# sensor.net
KiCad netlist of a schematic drawn in Altium Designer
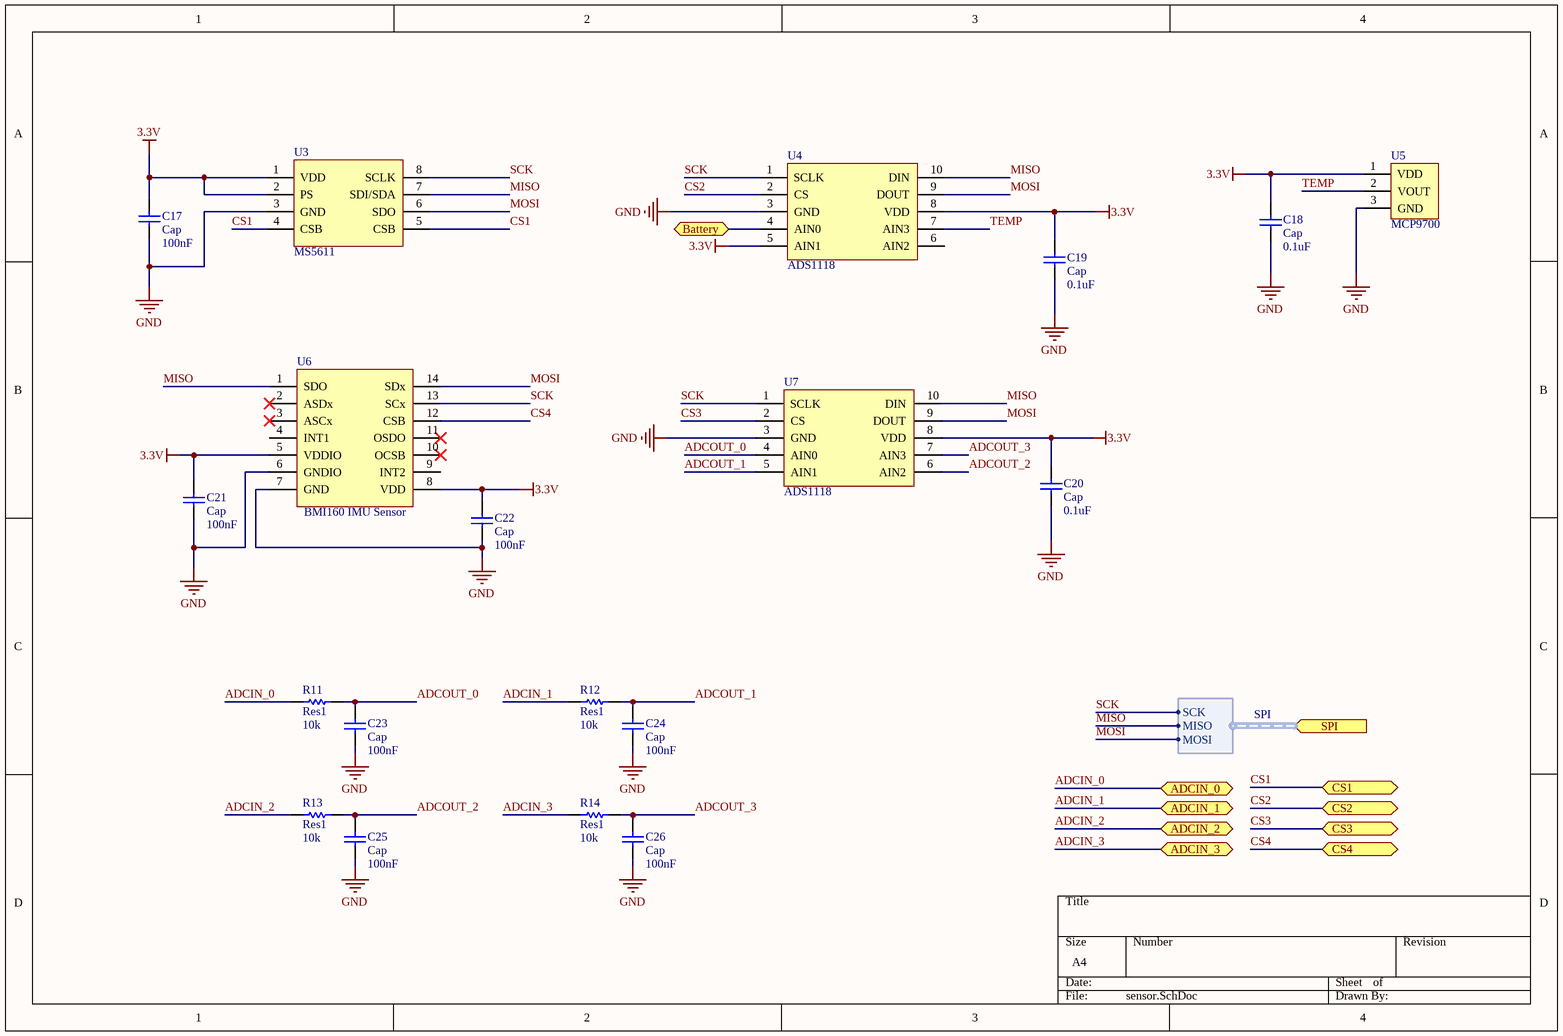
[diagram p0: sensor.SchDoc]

(export (version "E")
  (design (tool "Eeschema 10.0.6"))
  (components
    (comp (ref "C17")
      (value "Cap")
      (footprint "0805-CAP")
      (description "Capacitor")
      (fields (field (name "ALTIUM_VALUE") "100nF") (field (name "PUBLISHER") "Altium Limited"))
      (libsource (lib "Miscellaneous Devices") (part "Cap"))
    )
    (comp (ref "C18")
      (value "Cap")
      (footprint "0805-CAP")
      (description "Capacitor")
      (fields (field (name "ALTIUM_VALUE") "0.1uF") (field (name "PUBLISHER") "Altium Limited"))
      (libsource (lib "Miscellaneous Devices") (part "Cap"))
    )
    (comp (ref "C19")
      (value "Cap")
      (footprint "0805-CAP")
      (description "Capacitor")
      (fields (field (name "ALTIUM_VALUE") "0.1uF") (field (name "PUBLISHER") "Altium Limited"))
      (libsource (lib "Miscellaneous Devices") (part "Cap"))
    )
    (comp (ref "C20")
      (value "Cap")
      (footprint "0805-CAP")
      (description "Capacitor")
      (fields (field (name "ALTIUM_VALUE") "0.1uF") (field (name "PUBLISHER") "Altium Limited"))
      (libsource (lib "Miscellaneous Devices") (part "Cap"))
    )
    (comp (ref "C21")
      (value "Cap")
      (footprint "0805-CAP")
      (description "Capacitor")
      (fields (field (name "ALTIUM_VALUE") "100nF") (field (name "PUBLISHER") "Altium Limited"))
      (libsource (lib "Miscellaneous Devices") (part "Cap"))
    )
    (comp (ref "C22")
      (value "Cap")
      (footprint "0805-CAP")
      (description "Capacitor")
      (fields (field (name "ALTIUM_VALUE") "100nF") (field (name "PUBLISHER") "Altium Limited"))
      (libsource (lib "Miscellaneous Devices") (part "Cap"))
    )
    (comp (ref "C23")
      (value "Cap")
      (footprint "0805-CAP")
      (description "Capacitor")
      (fields (field (name "ALTIUM_VALUE") "100nF") (field (name "PUBLISHER") "Altium Limited"))
      (libsource (lib "Miscellaneous Devices") (part "Cap"))
    )
    (comp (ref "C24")
      (value "Cap")
      (footprint "0805-CAP")
      (description "Capacitor")
      (fields (field (name "ALTIUM_VALUE") "100nF") (field (name "PUBLISHER") "Altium Limited"))
      (libsource (lib "Miscellaneous Devices") (part "Cap"))
    )
    (comp (ref "C25")
      (value "Cap")
      (footprint "0805-CAP")
      (description "Capacitor")
      (fields (field (name "ALTIUM_VALUE") "100nF") (field (name "PUBLISHER") "Altium Limited"))
      (libsource (lib "Miscellaneous Devices") (part "Cap"))
    )
    (comp (ref "C26")
      (value "Cap")
      (footprint "0805-CAP")
      (description "Capacitor")
      (fields (field (name "ALTIUM_VALUE") "100nF") (field (name "PUBLISHER") "Altium Limited"))
      (libsource (lib "Miscellaneous Devices") (part "Cap"))
    )
    (comp (ref "R11")
      (value "Res1")
      (footprint "0805-RES")
      (description "Resistor")
      (fields (field (name "ALTIUM_VALUE") "10k") (field (name "PUBLISHER") "Altium Limited"))
      (libsource (lib "Miscellaneous Devices") (part "Res1"))
    )
    (comp (ref "R12")
      (value "Res1")
      (footprint "0805-RES")
      (description "Resistor")
      (fields (field (name "ALTIUM_VALUE") "10k") (field (name "PUBLISHER") "Altium Limited"))
      (libsource (lib "Miscellaneous Devices") (part "Res1"))
    )
    (comp (ref "R13")
      (value "Res1")
      (footprint "0805-RES")
      (description "Resistor")
      (fields (field (name "ALTIUM_VALUE") "10k") (field (name "PUBLISHER") "Altium Limited"))
      (libsource (lib "Miscellaneous Devices") (part "Res1"))
    )
    (comp (ref "R14")
      (value "Res1")
      (footprint "0805-RES")
      (description "Resistor")
      (fields (field (name "ALTIUM_VALUE") "10k") (field (name "PUBLISHER") "Altium Limited"))
      (libsource (lib "Miscellaneous Devices") (part "Res1"))
    )
    (comp (ref "U3")
      (value "MS5611")
      (footprint "MS5611-01BA03")
      (description "MS5611 Barometer I2C/SPI")
      (libsource (lib "Sensor-Schematics") (part "MS5611"))
    )
    (comp (ref "U4")
      (value "ADS1118")
      (footprint "MSOP10")
      (description "ADS1118 SPI 4 Channel ADC")
      (libsource (lib "") (part "ADS1118_1"))
    )
    (comp (ref "U5")
      (value "MCP9700")
      (footprint "SOT23-3 (TO-236AB)")
      (description "MCP9700 Linear Temperature Sensor")
      (libsource (lib "IC-Schematics") (part "MCP9700"))
    )
    (comp (ref "U6")
      (value "BMI160 IMU Sensor")
      (footprint "BMI160")
      (description "BoschTech BMI160 6 Axis IMU Sensor")
      (libsource (lib "Sensor-Schematics") (part "BMI160 IMU Sensor"))
    )
    (comp (ref "U7")
      (value "ADS1118")
      (footprint "MSOP10")
      (description "ADS1118 SPI 4 Channel ADC")
      (libsource (lib "IC-Schematics") (part "ADS1118"))
    )
  )
  (nets
    (net (code "2") (name "/ADCIN_0") (class "Default")
      (node (ref "R11") (pin "1") (pinfunction "1_1") (pintype "passive"))
    )
    (net (code "3") (name "/ADCIN_1") (class "Default")
      (node (ref "R12") (pin "1") (pinfunction "1_1") (pintype "passive"))
    )
    (net (code "4") (name "/ADCIN_2") (class "Default")
      (node (ref "R13") (pin "1") (pinfunction "1_1") (pintype "passive"))
    )
    (net (code "5") (name "/ADCIN_3") (class "Default")
      (node (ref "R14") (pin "1") (pinfunction "1_1") (pintype "passive"))
    )
    (net (code "6") (name "/ADCOUT_0") (class "Default")
      (node (ref "C23") (pin "1") (pinfunction "1_1") (pintype "passive"))
      (node (ref "R11") (pin "2") (pinfunction "2_2") (pintype "passive"))
      (node (ref "U7") (pin "4") (pinfunction "AIN0_4") (pintype "passive"))
    )
    (net (code "7") (name "/ADCOUT_1") (class "Default")
      (node (ref "C24") (pin "1") (pinfunction "1_1") (pintype "passive"))
      (node (ref "R12") (pin "2") (pinfunction "2_2") (pintype "passive"))
      (node (ref "U7") (pin "5") (pinfunction "AIN1_5") (pintype "passive"))
    )
    (net (code "8") (name "/ADCOUT_2") (class "Default")
      (node (ref "C25") (pin "1") (pinfunction "1_1") (pintype "passive"))
      (node (ref "R13") (pin "2") (pinfunction "2_2") (pintype "passive"))
      (node (ref "U7") (pin "6") (pinfunction "AIN2_6") (pintype "passive"))
    )
    (net (code "9") (name "/ADCOUT_3") (class "Default")
      (node (ref "C26") (pin "1") (pinfunction "1_1") (pintype "passive"))
      (node (ref "R14") (pin "2") (pinfunction "2_2") (pintype "passive"))
      (node (ref "U7") (pin "7") (pinfunction "AIN3_7") (pintype "passive"))
    )
    (net (code "10") (name "/Battery") (class "Default")
      (node (ref "U4") (pin "4") (pinfunction "AIN0_4") (pintype "passive"))
    )
    (net (code "11") (name "/CS1") (class "Default")
      (node (ref "U3") (pin "4") (pinfunction "CSB_4") (pintype "passive"))
      (node (ref "U3") (pin "5") (pinfunction "CSB_5") (pintype "passive"))
    )
    (net (code "12") (name "/CS2") (class "Default")
      (node (ref "U4") (pin "2") (pinfunction "CS_2") (pintype "passive"))
    )
    (net (code "13") (name "/CS3") (class "Default")
      (node (ref "U7") (pin "2") (pinfunction "CS_2") (pintype "passive"))
    )
    (net (code "14") (name "/CS4") (class "Default")
      (node (ref "U6") (pin "12") (pinfunction "CSB_12") (pintype "passive"))
    )
    (net (code "15") (name "/MISO") (class "Default")
      (node (ref "U3") (pin "7") (pinfunction "SDI/SDA_7") (pintype "passive"))
      (node (ref "U4") (pin "10") (pinfunction "DIN_10") (pintype "passive"))
      (node (ref "U6") (pin "1") (pinfunction "SDO_1") (pintype "passive"))
      (node (ref "U7") (pin "10") (pinfunction "DIN_10") (pintype "passive"))
    )
    (net (code "16") (name "/MOSI") (class "Default")
      (node (ref "U3") (pin "6") (pinfunction "SDO_6") (pintype "passive"))
      (node (ref "U4") (pin "9") (pinfunction "DOUT_9") (pintype "passive"))
      (node (ref "U6") (pin "14") (pinfunction "SDx_14") (pintype "passive"))
      (node (ref "U7") (pin "9") (pinfunction "DOUT_9") (pintype "passive"))
    )
    (net (code "17") (name "/SCK") (class "Default")
      (node (ref "U3") (pin "8") (pinfunction "SCLK_8") (pintype "passive"))
      (node (ref "U4") (pin "1") (pinfunction "SCLK_1") (pintype "passive"))
      (node (ref "U6") (pin "13") (pinfunction "SCx_13") (pintype "passive"))
      (node (ref "U7") (pin "1") (pinfunction "SCLK_1") (pintype "passive"))
    )
    (net (code "18") (name "/TEMP") (class "Default")
      (node (ref "U4") (pin "7") (pinfunction "AIN3_7") (pintype "passive"))
      (node (ref "U5") (pin "2") (pinfunction "VOUT_2") (pintype "passive"))
    )
    (net (code "20") (name "3.3V") (class "Default")
      (node (ref "C17") (pin "1") (pinfunction "1_1") (pintype "passive"))
      (node (ref "C18") (pin "1") (pinfunction "1_1") (pintype "passive"))
      (node (ref "C19") (pin "1") (pinfunction "1_1") (pintype "passive"))
      (node (ref "C20") (pin "1") (pinfunction "1_1") (pintype "passive"))
      (node (ref "C21") (pin "1") (pinfunction "1_1") (pintype "passive"))
      (node (ref "C22") (pin "1") (pinfunction "1_1") (pintype "passive"))
      (node (ref "U3") (pin "1") (pinfunction "VDD_1") (pintype "passive"))
      (node (ref "U3") (pin "2") (pinfunction "PS_2") (pintype "passive"))
      (node (ref "U4") (pin "5") (pinfunction "AIN1_5") (pintype "passive"))
      (node (ref "U4") (pin "8") (pinfunction "VDD_8") (pintype "passive"))
      (node (ref "U5") (pin "1") (pinfunction "VDD_1") (pintype "passive"))
      (node (ref "U6") (pin "5") (pinfunction "VDDIO_5") (pintype "passive"))
      (node (ref "U6") (pin "8") (pinfunction "VDD_8") (pintype "passive"))
      (node (ref "U7") (pin "8") (pinfunction "VDD_8") (pintype "passive"))
    )
    (net (code "21") (name "GND") (class "Default")
      (node (ref "C17") (pin "2") (pinfunction "2_2") (pintype "passive"))
      (node (ref "C18") (pin "2") (pinfunction "2_2") (pintype "passive"))
      (node (ref "C19") (pin "2") (pinfunction "2_2") (pintype "passive"))
      (node (ref "C20") (pin "2") (pinfunction "2_2") (pintype "passive"))
      (node (ref "C21") (pin "2") (pinfunction "2_2") (pintype "passive"))
      (node (ref "C22") (pin "2") (pinfunction "2_2") (pintype "passive"))
      (node (ref "C23") (pin "2") (pinfunction "2_2") (pintype "passive"))
      (node (ref "C24") (pin "2") (pinfunction "2_2") (pintype "passive"))
      (node (ref "C25") (pin "2") (pinfunction "2_2") (pintype "passive"))
      (node (ref "C26") (pin "2") (pinfunction "2_2") (pintype "passive"))
      (node (ref "U3") (pin "3") (pinfunction "GND_3") (pintype "passive"))
      (node (ref "U4") (pin "3") (pinfunction "GND_3") (pintype "passive"))
      (node (ref "U5") (pin "3") (pinfunction "GND_3") (pintype "passive"))
      (node (ref "U6") (pin "6") (pinfunction "GNDIO_6") (pintype "passive"))
      (node (ref "U6") (pin "7") (pinfunction "GND_7") (pintype "passive"))
      (node (ref "U7") (pin "3") (pinfunction "GND_3") (pintype "passive"))
    )
    (net (code "22") (name "unconnected-(U4-AIN2-Pad6)") (class "Default")
      (node (ref "U4") (pin "6") (pinfunction "AIN2_6") (pintype "passive"))
    )
    (net (code "23") (name "unconnected-(U6-ASCx-Pad3)") (class "Default")
      (node (ref "U6") (pin "3") (pinfunction "ASCx_3") (pintype "passive+no_connect"))
    )
    (net (code "24") (name "unconnected-(U6-ASDx-Pad2)") (class "Default")
      (node (ref "U6") (pin "2") (pinfunction "ASDx_2") (pintype "passive+no_connect"))
    )
    (net (code "25") (name "unconnected-(U6-INT1-Pad4)") (class "Default")
      (node (ref "U6") (pin "4") (pinfunction "INT1_4") (pintype "passive"))
    )
    (net (code "26") (name "unconnected-(U6-INT2-Pad9)") (class "Default")
      (node (ref "U6") (pin "9") (pinfunction "INT2_9") (pintype "passive"))
    )
    (net (code "27") (name "unconnected-(U6-OCSB-Pad10)") (class "Default")
      (node (ref "U6") (pin "10") (pinfunction "OCSB_10") (pintype "passive+no_connect"))
    )
    (net (code "28") (name "unconnected-(U6-OSDO-Pad11)") (class "Default")
      (node (ref "U6") (pin "11") (pinfunction "OSDO_11") (pintype "passive+no_connect"))
    )
  )
)
